# Astable_Clock.net
KiCad netlist of a schematic drawn in Altium Designer
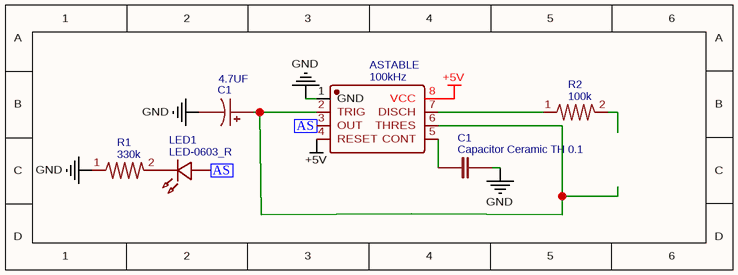
[diagram p0: Astable Clock.schdoc]

(export (version "E")
  (design (tool "Eeschema 10.0.6"))
  (components
    (comp (ref "4.7UF")
      (value "C1")
      (fields (field (name "CONTRIBUTOR") "syahindahaqilah97"))
      (libsource (lib "altium-import") (part "root_1_C1_"))
    )
    (comp (ref "ASTABLE")
      (value "100kHz")
      (fields (field (name "MANUFACTURER") "TI(德州仪器)") (field (name "MANUFACTURER PART") "NE555P"))
      (libsource (lib "altium-import") (part "root_0_100kHz_"))
    )
    (comp (ref "C1")
      (value "Capacitor Ceramic TH 0.1")
      (fields (field (name "MANUFACTURER PART") "?") (field (name "CONTRIBUTOR") "MelDuckmanton"))
      (libsource (lib "altium-import") (part "root_0_Capacitor Ceramic TH 0.1_"))
    )
    (comp (ref "LED1")
      (value "LED-0603_R")
      (fields
        (field (name "MANUFACTURER") "EVERLIGHT(台湾亿光)")
        (field (name "MANUFACTURER PART") "19-217/R6C-AL1M2VY/3T")
        (field (name "CONTRIBUTOR") "LCEDA_01")
      )
      (libsource (lib "altium-import") (part "root_2_LED-0603_R_"))
    )
    (comp (ref "R1")
      (value "330k")
      (fields (field (name "CONTRIBUTOR") "Saepul Hidayat"))
      (libsource (lib "altium-import") (part "root_1_330k_"))
    )
    (comp (ref "R2")
      (value "100k")
      (fields (field (name "CONTRIBUTOR") "Saepul Hidayat"))
      (libsource (lib "altium-import") (part "root_1_100k_"))
    )
  )
  (nets
    (net (code "1") (name "+5V") (class "Default")
      (node (ref "ASTABLE") (pin "4") (pinfunction "RESET_4") (pintype "passive"))
      (node (ref "ASTABLE") (pin "8") (pinfunction "VCC_8") (pintype "passive"))
    )
    (net (code "2") (name "/AS") (class "Default")
      (node (ref "ASTABLE") (pin "3") (pinfunction "OUT_3") (pintype "passive"))
      (node (ref "LED1") (pin "1") (pinfunction "1_1") (pintype "passive"))
    )
    (net (code "3") (name "GND") (class "Default")
      (node (ref "4.7UF") (pin "2") (pinfunction "2_2") (pintype "passive"))
      (node (ref "ASTABLE") (pin "1") (pinfunction "GND_1") (pintype "passive"))
      (node (ref "C1") (pin "2") (pinfunction "2_2") (pintype "passive"))
      (node (ref "R1") (pin "1") (pinfunction "1_1") (pintype "passive"))
    )
    (net (code "4") (name "Net-(ASTABLE-CONT)") (class "Default")
      (node (ref "ASTABLE") (pin "5") (pinfunction "CONT_5") (pintype "passive"))
      (node (ref "C1") (pin "1") (pinfunction "1_1") (pintype "passive"))
    )
    (net (code "5") (name "Net-(ASTABLE-DISCH)") (class "Default")
      (node (ref "ASTABLE") (pin "7") (pinfunction "DISCH_7") (pintype "passive"))
      (node (ref "R2") (pin "1") (pinfunction "1_1") (pintype "passive"))
    )
    (net (code "6") (name "Net-(ASTABLE-THRES)") (class "Default")
      (node (ref "4.7UF") (pin "1") (pinfunction "1_1") (pintype "passive"))
      (node (ref "ASTABLE") (pin "2") (pinfunction "TRIG_2") (pintype "passive"))
      (node (ref "ASTABLE") (pin "6") (pinfunction "THRES_6") (pintype "passive"))
    )
    (net (code "7") (name "Net-(LED1-Pad2)") (class "Default")
      (node (ref "LED1") (pin "2") (pinfunction "2_2") (pintype "passive"))
      (node (ref "R1") (pin "2") (pinfunction "2_2") (pintype "passive"))
    )
    (net (code "8") (name "unconnected-(R2-Pad2)") (class "Default")
      (node (ref "R2") (pin "2") (pinfunction "2_2") (pintype "passive"))
    )
  )
)
